# ECG_V5.net
KiCad netlist of a schematic drawn in EAGLE
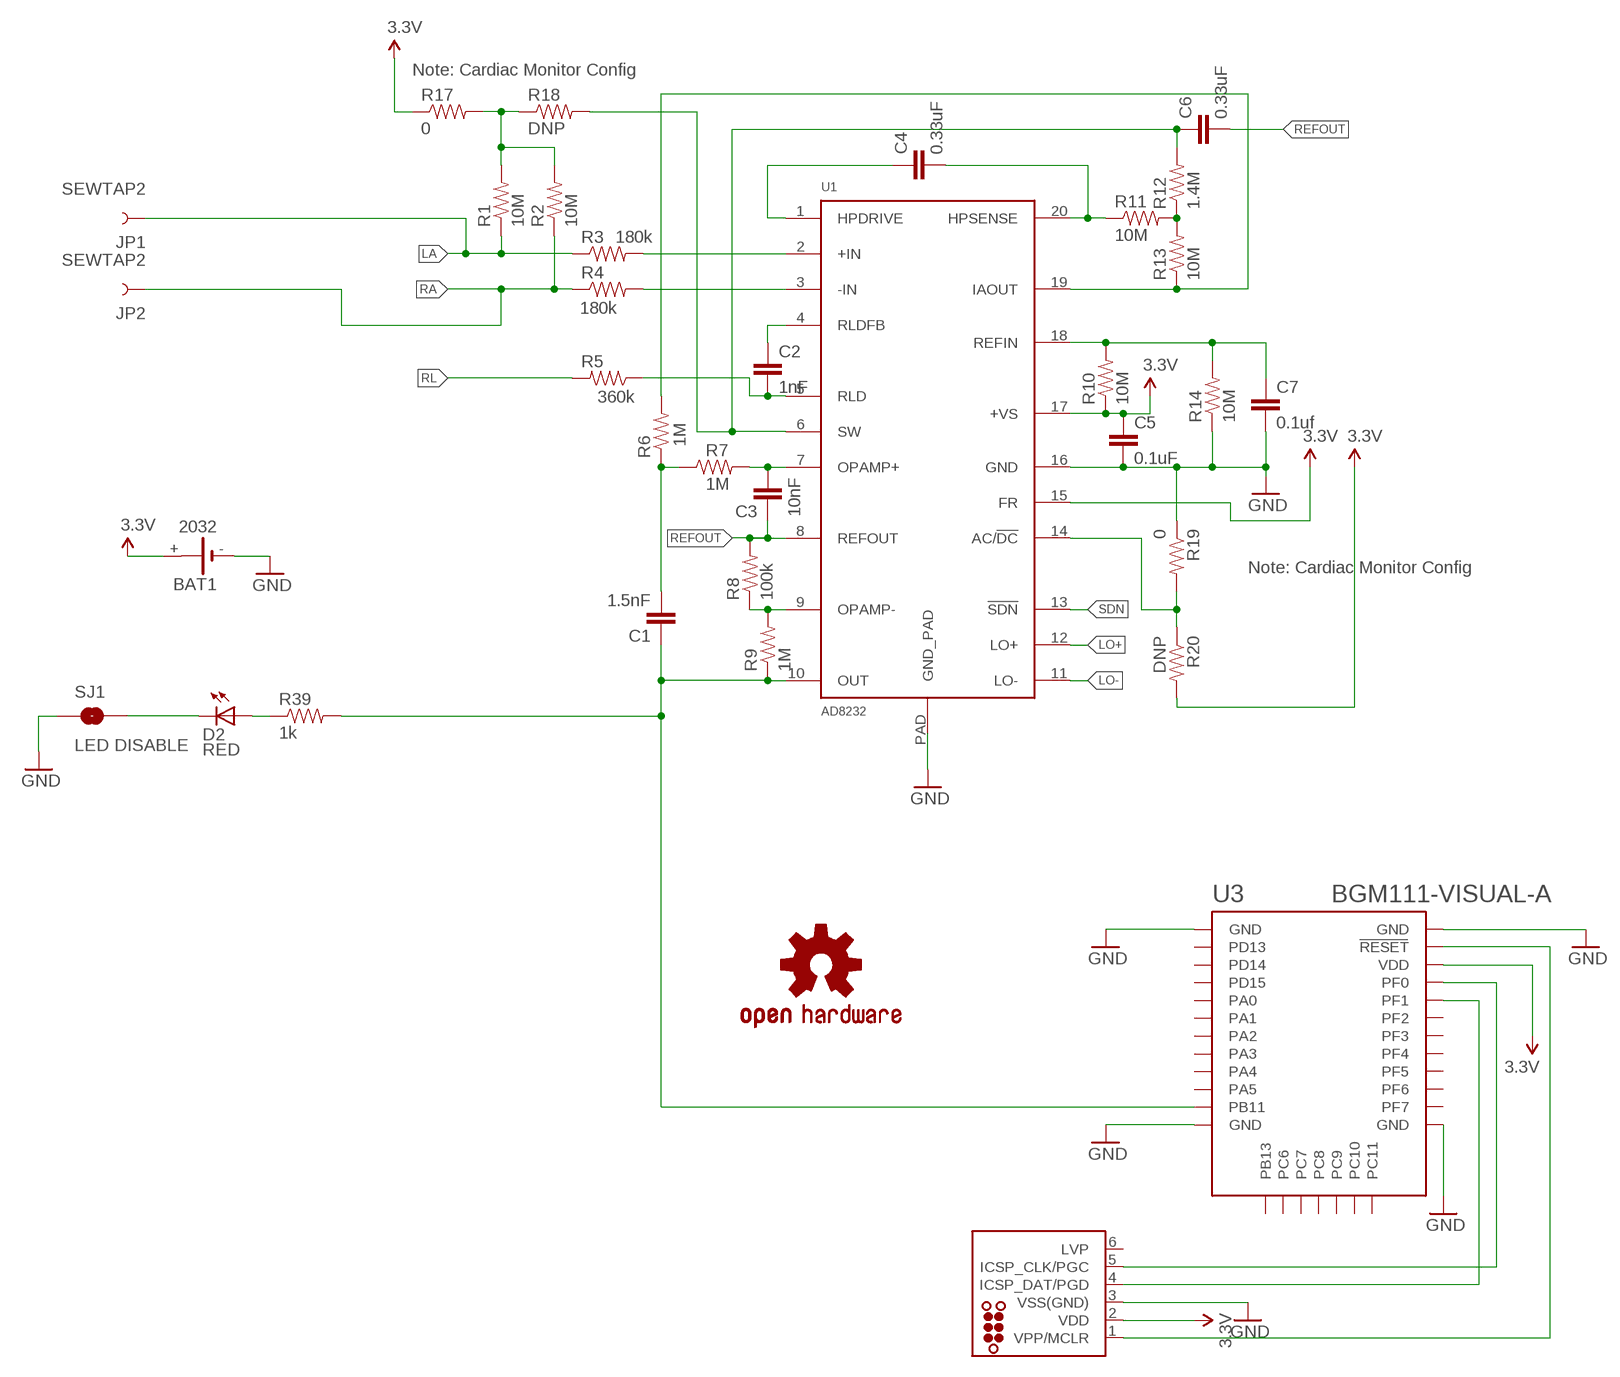
[diagram p0: schematic, sheet 1]

(export (version "E")
  (design (tool "Eeschema 10.0.6"))
  (components
    (comp (ref "BAT1")
      (value "2032")
      (footprint "eagle-import:KZH20SMD")
      (libsource (lib "eagle-import") (part "2032"))
    )
    (comp (ref "C1")
      (value "1.5nF")
      (footprint "eagle-import:0603-CAP")
      (libsource (lib "eagle-import") (part "CAP0603-CAP"))
    )
    (comp (ref "C2")
      (value "1nF")
      (footprint "eagle-import:0603-CAP")
      (libsource (lib "eagle-import") (part "CAP0603-CAP"))
    )
    (comp (ref "C3")
      (value "10nF")
      (footprint "eagle-import:0603-CAP")
      (libsource (lib "eagle-import") (part "CAP0603-CAP"))
    )
    (comp (ref "C4")
      (value "0.33uF")
      (footprint "eagle-import:0805")
      (libsource (lib "eagle-import") (part "CAP0805"))
    )
    (comp (ref "C5")
      (value "0.1uF")
      (footprint "eagle-import:0603-CAP")
      (libsource (lib "eagle-import") (part "CAP0603-CAP"))
    )
    (comp (ref "C6")
      (value "0.33uF")
      (footprint "eagle-import:0805")
      (libsource (lib "eagle-import") (part "CAP0805"))
    )
    (comp (ref "C7")
      (value "0.1uf")
      (footprint "eagle-import:0603-CAP")
      (libsource (lib "eagle-import") (part "CAP0603-CAP"))
    )
    (comp (ref "D2")
      (value "RED")
      (footprint "eagle-import:LED-0603")
      (libsource (lib "eagle-import") (part "LED-RED0603"))
    )
    (comp (ref "J2")
      (value "TC2030-MCP-NL")
      (footprint "eagle-import:TC2030-MCP-NL")
      (libsource (lib "eagle-import") (part "TC2030-MCP-NL"))
    )
    (comp (ref "JP1")
      (value "SEWTAP2")
      (footprint "eagle-import:PETAL-LONG-2")
      (libsource (lib "eagle-import") (part "SEWTAP2"))
    )
    (comp (ref "JP2")
      (value "SEWTAP2")
      (footprint "eagle-import:PETAL-LONG-2")
      (libsource (lib "eagle-import") (part "SEWTAP2"))
    )
    (comp (ref "LOGO1")
      (value "OSHW-LOGOS")
      (footprint "eagle-import:OSHW-LOGO-S")
      (libsource (lib "eagle-import") (part "OSHW-LOGOS"))
    )
    (comp (ref "R1")
      (value "10M")
      (footprint "eagle-import:0603-RES")
      (libsource (lib "eagle-import") (part "RESISTOR0603-RES"))
    )
    (comp (ref "R2")
      (value "10M")
      (footprint "eagle-import:0603-RES")
      (libsource (lib "eagle-import") (part "RESISTOR0603-RES"))
    )
    (comp (ref "R3")
      (value "180k")
      (footprint "eagle-import:0603-RES")
      (libsource (lib "eagle-import") (part "RESISTOR0603-RES"))
    )
    (comp (ref "R4")
      (value "180k")
      (footprint "eagle-import:0603-RES")
      (libsource (lib "eagle-import") (part "RESISTOR0603-RES"))
    )
    (comp (ref "R5")
      (value "360k")
      (footprint "eagle-import:0603-RES")
      (libsource (lib "eagle-import") (part "RESISTOR0603-RES"))
    )
    (comp (ref "R6")
      (value "1M")
      (footprint "eagle-import:0603-RES")
      (libsource (lib "eagle-import") (part "RESISTOR0603-RES"))
    )
    (comp (ref "R7")
      (value "1M")
      (footprint "eagle-import:0603-RES")
      (libsource (lib "eagle-import") (part "RESISTOR0603-RES"))
    )
    (comp (ref "R8")
      (value "100k")
      (footprint "eagle-import:0603-RES")
      (libsource (lib "eagle-import") (part "RESISTOR0603-RES"))
    )
    (comp (ref "R9")
      (value "1M")
      (footprint "eagle-import:0603-RES")
      (libsource (lib "eagle-import") (part "RESISTOR0603-RES"))
    )
    (comp (ref "R10")
      (value "10M")
      (footprint "eagle-import:0603-RES")
      (libsource (lib "eagle-import") (part "RESISTOR0603-RES"))
    )
    (comp (ref "R11")
      (value "10M")
      (footprint "eagle-import:0603-RES")
      (libsource (lib "eagle-import") (part "RESISTOR0603-RES"))
    )
    (comp (ref "R12")
      (value "1.4M")
      (footprint "eagle-import:0603-RES")
      (libsource (lib "eagle-import") (part "RESISTOR0603-RES"))
    )
    (comp (ref "R13")
      (value "10M")
      (footprint "eagle-import:0603-RES")
      (libsource (lib "eagle-import") (part "RESISTOR0603-RES"))
    )
    (comp (ref "R14")
      (value "10M")
      (footprint "eagle-import:0603-RES")
      (libsource (lib "eagle-import") (part "RESISTOR0603-RES"))
    )
    (comp (ref "R17")
      (value "0")
      (footprint "eagle-import:0603")
      (libsource (lib "eagle-import") (part "0OHM1/10W5%(0603)"))
    )
    (comp (ref "R18")
      (value "DNP")
      (footprint "eagle-import:0603")
      (libsource (lib "eagle-import") (part "0OHM1/10W5%(0603)"))
    )
    (comp (ref "R19")
      (value "0")
      (footprint "eagle-import:0603")
      (libsource (lib "eagle-import") (part "0OHM1/10W5%(0603)"))
    )
    (comp (ref "R20")
      (value "DNP")
      (footprint "eagle-import:0603")
      (libsource (lib "eagle-import") (part "0OHM1/10W5%(0603)"))
    )
    (comp (ref "R39")
      (value "1k")
      (footprint "eagle-import:0603-RES")
      (libsource (lib "eagle-import") (part "1K-1%"))
    )
    (comp (ref "SJ1")
      (value "LED DISABLE")
      (footprint "eagle-import:SJ_2S-TRACE")
      (libsource (lib "eagle-import") (part "SOLDERJUMPERTRACE"))
    )
    (comp (ref "U1")
      (value "AD8232")
      (footprint "eagle-import:LFCSP_20")
      (libsource (lib "eagle-import") (part "AD8232"))
    )
    (comp (ref "U3")
      (value "BGM111-VISUAL-A")
      (footprint "eagle-import:BGM111-A")
      (libsource (lib "eagle-import") (part "BGM111-VISUAL-A"))
    )
  )
  (nets
    (net (code "1") (name "3.3V") (class "Default")
      (node (ref "BAT1") (pin "+") (pinfunction "+_+") (pintype "passive"))
      (node (ref "C5") (pin "1") (pinfunction "1_1") (pintype "passive"))
      (node (ref "J2") (pin "2") (pinfunction "VDD_2") (pintype "power_in"))
      (node (ref "R10") (pin "1") (pinfunction "1_1") (pintype "passive"))
      (node (ref "R17") (pin "1") (pinfunction "1_1") (pintype "passive"))
      (node (ref "R20") (pin "2") (pinfunction "2_2") (pintype "passive"))
      (node (ref "U1") (pin "15") (pinfunction "FR_15") (pintype "bidirectional"))
      (node (ref "U1") (pin "17") (pinfunction "+VS_17") (pintype "bidirectional"))
      (node (ref "U3") (pin "VDD") (pinfunction "VDD_VDD") (pintype "power_in"))
    )
    (net (code "2") (name "GND") (class "Default")
      (node (ref "BAT1") (pin "-") (pinfunction "-_-") (pintype "passive"))
      (node (ref "C5") (pin "2") (pinfunction "2_2") (pintype "passive"))
      (node (ref "C7") (pin "2") (pinfunction "2_2") (pintype "passive"))
      (node (ref "J2") (pin "3") (pinfunction "VSS(GND)_3") (pintype "power_in"))
      (node (ref "R14") (pin "1") (pinfunction "1_1") (pintype "passive"))
      (node (ref "R19") (pin "1") (pinfunction "1_1") (pintype "passive"))
      (node (ref "SJ1") (pin "1") (pinfunction "1_1") (pintype "passive"))
      (node (ref "U1") (pin "16") (pinfunction "GND_16") (pintype "bidirectional"))
      (node (ref "U1") (pin "PAD") (pinfunction "GND_PAD_PAD") (pintype "bidirectional"))
      (node (ref "U3") (pin "GND") (pinfunction "GND_GND") (pintype "power_in"))
      (node (ref "U3") (pin "GND@2") (pinfunction "GND_GND@2") (pintype "power_in"))
      (node (ref "U3") (pin "GND@3") (pinfunction "GND_GND@3") (pintype "power_in"))
      (node (ref "U3") (pin "GND@4") (pinfunction "GND_GND@4") (pintype "power_in"))
    )
    (net (code "3") (name "LA") (class "Default")
      (node (ref "JP1") (pin "1") (pinfunction "1_1") (pintype "bidirectional"))
      (node (ref "R1") (pin "1") (pinfunction "1_1") (pintype "passive"))
      (node (ref "R3") (pin "1") (pinfunction "1_1") (pintype "passive"))
    )
    (net (code "4") (name "LO+") (class "Default")
      (node (ref "U1") (pin "12") (pinfunction "LO+_12") (pintype "bidirectional"))
    )
    (net (code "5") (name "LO-") (class "Default")
      (node (ref "U1") (pin "11") (pinfunction "LO-_11") (pintype "bidirectional"))
    )
    (net (code "6") (name "Net-(C1-Pad2)") (class "Default")
      (node (ref "C1") (pin "2") (pinfunction "2_2") (pintype "passive"))
      (node (ref "R6") (pin "1") (pinfunction "1_1") (pintype "passive"))
      (node (ref "R7") (pin "1") (pinfunction "1_1") (pintype "passive"))
    )
    (net (code "7") (name "Net-(D2-PadA)") (class "Default")
      (node (ref "D2") (pin "A") (pinfunction "A_A") (pintype "passive"))
      (node (ref "R39") (pin "1") (pinfunction "1_1") (pintype "passive"))
    )
    (net (code "8") (name "Net-(D2-PadC)") (class "Default")
      (node (ref "D2") (pin "C") (pinfunction "C_C") (pintype "passive"))
      (node (ref "SJ1") (pin "2") (pinfunction "2_2") (pintype "passive"))
    )
    (net (code "9") (name "Net-(J2-ICSP_CLK{slash}PGC)") (class "Default")
      (node (ref "J2") (pin "5") (pinfunction "ICSP_CLK/PGC_5") (pintype "output"))
      (node (ref "U3") (pin "PF0") (pinfunction "PF0_PF0") (pintype "bidirectional"))
    )
    (net (code "10") (name "Net-(J2-ICSP_DAT{slash}PGD)") (class "Default")
      (node (ref "J2") (pin "4") (pinfunction "ICSP_DAT/PGD_4") (pintype "bidirectional"))
      (node (ref "U3") (pin "PF1") (pinfunction "PF1_PF1") (pintype "bidirectional"))
    )
    (net (code "11") (name "Net-(J2-VPP{slash}MCLR)") (class "Default")
      (node (ref "J2") (pin "1") (pinfunction "VPP/MCLR_1") (pintype "passive"))
      (node (ref "U3") (pin "RESET") (pinfunction "RESET_RESET") (pintype "input"))
    )
    (net (code "12") (name "Net-(R1-Pad2)") (class "Default")
      (node (ref "R1") (pin "2") (pinfunction "2_2") (pintype "passive"))
      (node (ref "R17") (pin "2") (pinfunction "2_2") (pintype "passive"))
      (node (ref "R18") (pin "1") (pinfunction "1_1") (pintype "passive"))
      (node (ref "R2") (pin "2") (pinfunction "2_2") (pintype "passive"))
    )
    (net (code "13") (name "Net-(R11-Pad2)") (class "Default")
      (node (ref "R11") (pin "2") (pinfunction "2_2") (pintype "passive"))
      (node (ref "R12") (pin "1") (pinfunction "1_1") (pintype "passive"))
      (node (ref "R13") (pin "2") (pinfunction "2_2") (pintype "passive"))
    )
    (net (code "14") (name "Net-(U1-+IN)") (class "Default")
      (node (ref "R3") (pin "2") (pinfunction "2_2") (pintype "passive"))
      (node (ref "U1") (pin "2") (pinfunction "+IN_2") (pintype "bidirectional"))
    )
    (net (code "15") (name "Net-(U1--IN)") (class "Default")
      (node (ref "R4") (pin "2") (pinfunction "2_2") (pintype "passive"))
      (node (ref "U1") (pin "3") (pinfunction "-IN_3") (pintype "bidirectional"))
    )
    (net (code "16") (name "Net-(U1-AC{slash}~{DC})") (class "Default")
      (node (ref "R19") (pin "2") (pinfunction "2_2") (pintype "passive"))
      (node (ref "R20") (pin "1") (pinfunction "1_1") (pintype "passive"))
      (node (ref "U1") (pin "14") (pinfunction "AC/~{DC}_14") (pintype "bidirectional"))
    )
    (net (code "17") (name "Net-(U1-HPDRIVE)") (class "Default")
      (node (ref "C4") (pin "1") (pinfunction "1_1") (pintype "passive"))
      (node (ref "U1") (pin "1") (pinfunction "HPDRIVE_1") (pintype "bidirectional"))
    )
    (net (code "18") (name "Net-(U1-HPSENSE)") (class "Default")
      (node (ref "C4") (pin "2") (pinfunction "2_2") (pintype "passive"))
      (node (ref "R11") (pin "1") (pinfunction "1_1") (pintype "passive"))
      (node (ref "U1") (pin "20") (pinfunction "HPSENSE_20") (pintype "bidirectional"))
    )
    (net (code "19") (name "Net-(U1-IAOUT)") (class "Default")
      (node (ref "R13") (pin "1") (pinfunction "1_1") (pintype "passive"))
      (node (ref "R6") (pin "2") (pinfunction "2_2") (pintype "passive"))
      (node (ref "U1") (pin "19") (pinfunction "IAOUT_19") (pintype "bidirectional"))
    )
    (net (code "20") (name "Net-(U1-OPAMP+)") (class "Default")
      (node (ref "C3") (pin "2") (pinfunction "2_2") (pintype "passive"))
      (node (ref "R7") (pin "2") (pinfunction "2_2") (pintype "passive"))
      (node (ref "U1") (pin "7") (pinfunction "OPAMP+_7") (pintype "bidirectional"))
    )
    (net (code "21") (name "Net-(U1-OPAMP-)") (class "Default")
      (node (ref "R8") (pin "1") (pinfunction "1_1") (pintype "passive"))
      (node (ref "R9") (pin "2") (pinfunction "2_2") (pintype "passive"))
      (node (ref "U1") (pin "9") (pinfunction "OPAMP-_9") (pintype "bidirectional"))
    )
    (net (code "22") (name "Net-(U1-OUT)") (class "Default")
      (node (ref "C1") (pin "1") (pinfunction "1_1") (pintype "passive"))
      (node (ref "R39") (pin "2") (pinfunction "2_2") (pintype "passive"))
      (node (ref "R9") (pin "1") (pinfunction "1_1") (pintype "passive"))
      (node (ref "U1") (pin "10") (pinfunction "OUT_10") (pintype "bidirectional"))
      (node (ref "U3") (pin "PB11") (pinfunction "PB11_PB11") (pintype "bidirectional"))
    )
    (net (code "23") (name "Net-(U1-REFIN)") (class "Default")
      (node (ref "C7") (pin "1") (pinfunction "1_1") (pintype "passive"))
      (node (ref "R10") (pin "2") (pinfunction "2_2") (pintype "passive"))
      (node (ref "R14") (pin "2") (pinfunction "2_2") (pintype "passive"))
      (node (ref "U1") (pin "18") (pinfunction "REFIN_18") (pintype "bidirectional"))
    )
    (net (code "24") (name "Net-(U1-RLD)") (class "Default")
      (node (ref "C2") (pin "2") (pinfunction "2_2") (pintype "passive"))
      (node (ref "R5") (pin "1") (pinfunction "1_1") (pintype "passive"))
      (node (ref "U1") (pin "5") (pinfunction "RLD_5") (pintype "bidirectional"))
    )
    (net (code "25") (name "Net-(U1-RLDFB)") (class "Default")
      (node (ref "C2") (pin "1") (pinfunction "1_1") (pintype "passive"))
      (node (ref "U1") (pin "4") (pinfunction "RLDFB_4") (pintype "bidirectional"))
    )
    (net (code "26") (name "Net-(U1-SW)") (class "Default")
      (node (ref "C6") (pin "1") (pinfunction "1_1") (pintype "passive"))
      (node (ref "R12") (pin "2") (pinfunction "2_2") (pintype "passive"))
      (node (ref "R18") (pin "2") (pinfunction "2_2") (pintype "passive"))
      (node (ref "U1") (pin "6") (pinfunction "SW_6") (pintype "bidirectional"))
    )
    (net (code "27") (name "RA") (class "Default")
      (node (ref "JP2") (pin "1") (pinfunction "1_1") (pintype "bidirectional"))
      (node (ref "R2") (pin "1") (pinfunction "1_1") (pintype "passive"))
      (node (ref "R4") (pin "1") (pinfunction "1_1") (pintype "passive"))
    )
    (net (code "28") (name "REFOUT") (class "Default")
      (node (ref "C3") (pin "1") (pinfunction "1_1") (pintype "passive"))
      (node (ref "C6") (pin "2") (pinfunction "2_2") (pintype "passive"))
      (node (ref "R8") (pin "2") (pinfunction "2_2") (pintype "passive"))
      (node (ref "U1") (pin "8") (pinfunction "REFOUT_8") (pintype "bidirectional"))
    )
    (net (code "29") (name "RL") (class "Default")
      (node (ref "R5") (pin "2") (pinfunction "2_2") (pintype "passive"))
    )
    (net (code "30") (name "SDN") (class "Default")
      (node (ref "U1") (pin "13") (pinfunction "~{SDN}_13") (pintype "bidirectional"))
    )
    (net (code "31") (name "unconnected-(J2-LVP-Pad6)") (class "Default")
      (node (ref "J2") (pin "6") (pinfunction "LVP_6") (pintype "bidirectional"))
    )
    (net (code "32") (name "unconnected-(U3-PadPA0)") (class "Default")
      (node (ref "U3") (pin "PA0") (pinfunction "PA0_PA0") (pintype "bidirectional"))
    )
    (net (code "33") (name "unconnected-(U3-PadPA1)") (class "Default")
      (node (ref "U3") (pin "PA1") (pinfunction "PA1_PA1") (pintype "bidirectional"))
    )
    (net (code "34") (name "unconnected-(U3-PadPA2)") (class "Default")
      (node (ref "U3") (pin "PA2") (pinfunction "PA2_PA2") (pintype "bidirectional"))
    )
    (net (code "35") (name "unconnected-(U3-PadPA3)") (class "Default")
      (node (ref "U3") (pin "PA3") (pinfunction "PA3_PA3") (pintype "bidirectional"))
    )
    (net (code "36") (name "unconnected-(U3-PadPA4)") (class "Default")
      (node (ref "U3") (pin "PA4") (pinfunction "PA4_PA4") (pintype "bidirectional"))
    )
    (net (code "37") (name "unconnected-(U3-PadPA5)") (class "Default")
      (node (ref "U3") (pin "PA5") (pinfunction "PA5_PA5") (pintype "bidirectional"))
    )
    (net (code "38") (name "unconnected-(U3-PadPB13)") (class "Default")
      (node (ref "U3") (pin "PB13") (pinfunction "PB13_PB13") (pintype "bidirectional"))
    )
    (net (code "39") (name "unconnected-(U3-PadPC6)") (class "Default")
      (node (ref "U3") (pin "PC6") (pinfunction "PC6_PC6") (pintype "bidirectional"))
    )
    (net (code "40") (name "unconnected-(U3-PadPC7)") (class "Default")
      (node (ref "U3") (pin "PC7") (pinfunction "PC7_PC7") (pintype "bidirectional"))
    )
    (net (code "41") (name "unconnected-(U3-PadPC8)") (class "Default")
      (node (ref "U3") (pin "PC8") (pinfunction "PC8_PC8") (pintype "bidirectional"))
    )
    (net (code "42") (name "unconnected-(U3-PadPC9)") (class "Default")
      (node (ref "U3") (pin "PC9") (pinfunction "PC9_PC9") (pintype "bidirectional"))
    )
    (net (code "43") (name "unconnected-(U3-PadPC10)") (class "Default")
      (node (ref "U3") (pin "PC10") (pinfunction "PC10_PC10") (pintype "bidirectional"))
    )
    (net (code "44") (name "unconnected-(U3-PadPC11)") (class "Default")
      (node (ref "U3") (pin "PC11") (pinfunction "PC11_PC11") (pintype "bidirectional"))
    )
    (net (code "45") (name "unconnected-(U3-PadPD13)") (class "Default")
      (node (ref "U3") (pin "PD13") (pinfunction "PD13_PD13") (pintype "bidirectional"))
    )
    (net (code "46") (name "unconnected-(U3-PadPD14)") (class "Default")
      (node (ref "U3") (pin "PD14") (pinfunction "PD14_PD14") (pintype "bidirectional"))
    )
    (net (code "47") (name "unconnected-(U3-PadPD15)") (class "Default")
      (node (ref "U3") (pin "PD15") (pinfunction "PD15_PD15") (pintype "bidirectional"))
    )
    (net (code "48") (name "unconnected-(U3-PadPF2)") (class "Default")
      (node (ref "U3") (pin "PF2") (pinfunction "PF2_PF2") (pintype "bidirectional"))
    )
    (net (code "49") (name "unconnected-(U3-PadPF3)") (class "Default")
      (node (ref "U3") (pin "PF3") (pinfunction "PF3_PF3") (pintype "bidirectional"))
    )
    (net (code "50") (name "unconnected-(U3-PadPF4)") (class "Default")
      (node (ref "U3") (pin "PF4") (pinfunction "PF4_PF4") (pintype "bidirectional"))
    )
    (net (code "51") (name "unconnected-(U3-PadPF5)") (class "Default")
      (node (ref "U3") (pin "PF5") (pinfunction "PF5_PF5") (pintype "bidirectional"))
    )
    (net (code "52") (name "unconnected-(U3-PadPF6)") (class "Default")
      (node (ref "U3") (pin "PF6") (pinfunction "PF6_PF6") (pintype "bidirectional"))
    )
    (net (code "53") (name "unconnected-(U3-PadPF7)") (class "Default")
      (node (ref "U3") (pin "PF7") (pinfunction "PF7_PF7") (pintype "bidirectional"))
    )
  )
)
